# RoBeast_UI.net
KiCad netlist of a schematic drawn in Altium Designer
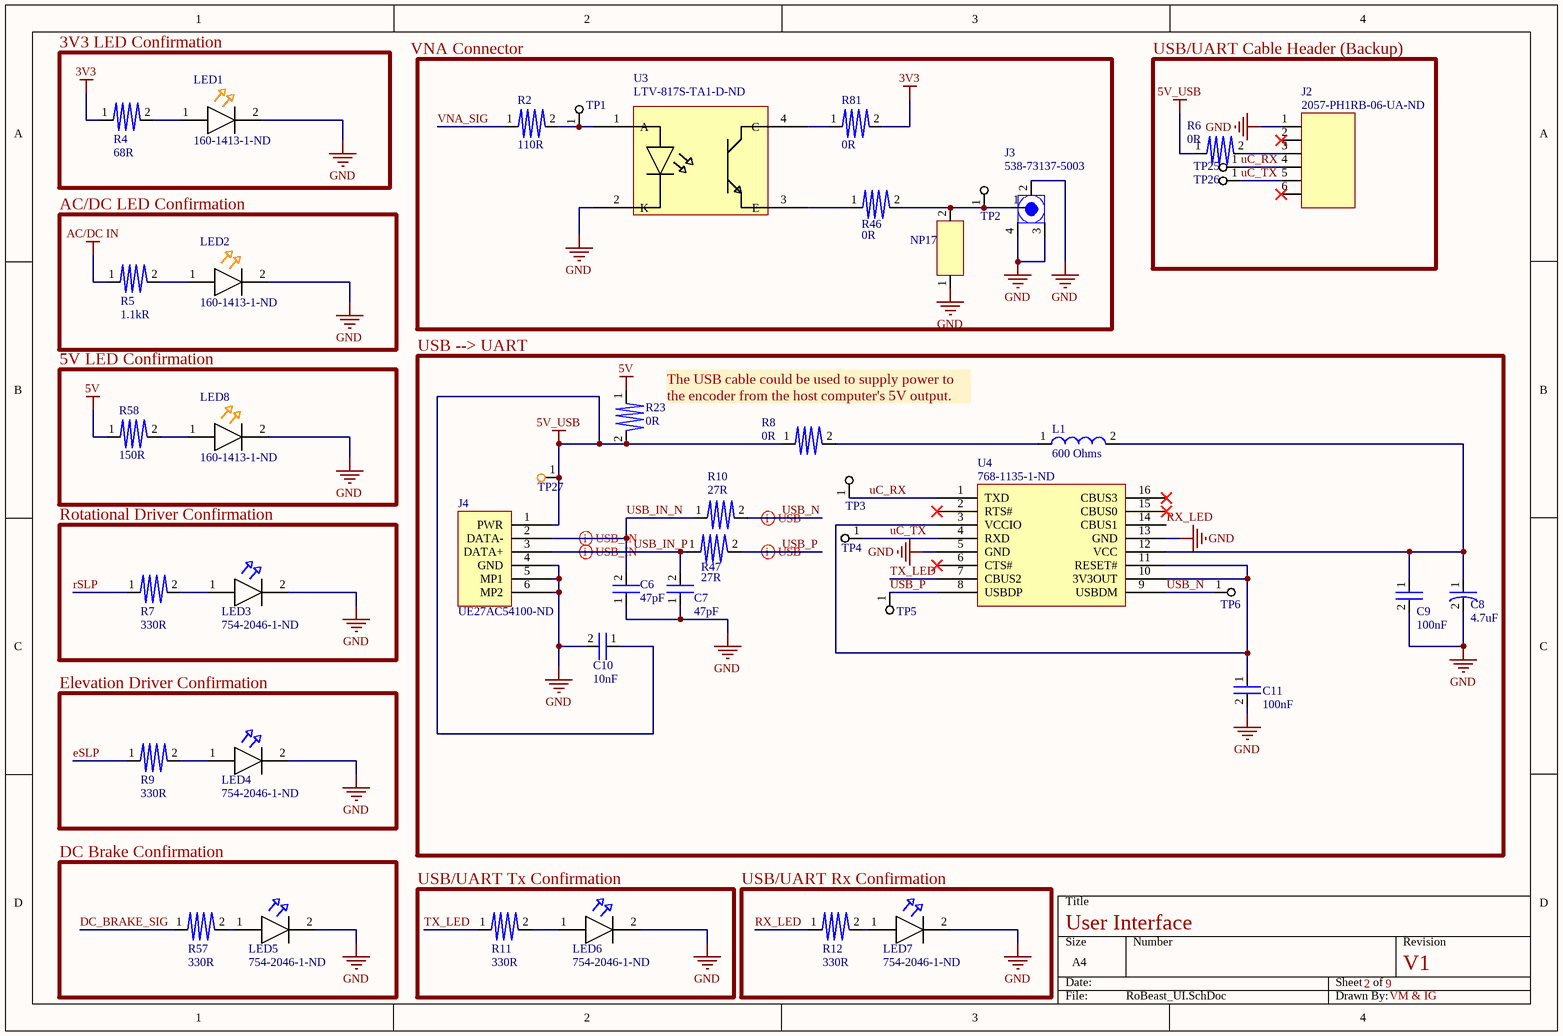
[diagram p0: RoBeast_UI.SchDoc]

(export (version "E")
  (design (tool "Eeschema 10.0.6"))
  (components
    (comp (ref "C6")
      (value "47pF")
      (footprint "0805")
      (fields
        (field (name "MANUFACTURER") "KEMET")
        (field (name "MANUFACTURER PART NUMBER") "C0805C470J5GAC7210")
      )
      (libsource (lib "RoBeast_Schematic_Library") (part "C0805C470J5GAC7210"))
    )
    (comp (ref "C7")
      (value "47pF")
      (footprint "0805")
      (fields
        (field (name "MANUFACTURER") "KEMET")
        (field (name "MANUFACTURER PART NUMBER") "C0805C470J5GAC7210")
      )
      (libsource (lib "RoBeast_Schematic_Library") (part "C0805C470J5GAC7210"))
    )
    (comp (ref "C8")
      (value "4.7uF")
      (footprint "EDK475M050A9DAA")
      (fields
        (field (name "MANUFACTURER") "KEMET")
        (field (name "MANUFACTURER PART NUMBER") "EDK475M050A9DAA")
      )
      (libsource (lib "RoBeast_Schematic_Library") (part "EDK475M050A9DAA"))
    )
    (comp (ref "C9")
      (value "100nF")
      (footprint "0805")
      (fields
        (field (name "MANUFACTURER") "KEMET")
        (field (name "MANUFACTURER PART NUMBER") "C0805C104J5RACTU")
      )
      (libsource (lib "RoBeast_Schematic_Library") (part "C0805C104J5RAC7800"))
    )
    (comp (ref "C10")
      (value "10nF")
      (footprint "0805")
      (fields
        (field (name "MANUFACTURER") "KEMET")
        (field (name "MANUFACTURER PART NUMBER") "C0805C103J5RAC7210")
      )
      (libsource (lib "RoBeast_Schematic_Library") (part "C0805C103J5RAC7210"))
    )
    (comp (ref "C11")
      (value "100nF")
      (footprint "0805")
      (fields
        (field (name "MANUFACTURER") "KEMET")
        (field (name "MANUFACTURER PART NUMBER") "C0805C104J5RACTU")
      )
      (libsource (lib "RoBeast_Schematic_Library") (part "C0805C104J5RAC7800"))
    )
    (comp (ref "J2")
      (value "6 Pin Connector")
      (footprint "PH1RB-06-UA")
      (description "Conn Unshrouded Header HDR 6 POS 2.54mm Solder RA Thru-Hole")
      (fields
        (field (name "MANUFACTURER") "Adam Equipment")
        (field (name "MANUFACTURER PART NUMBER") "PH1RB-06-UA")
        (field (name "SUPPLIER PART NUMBER 1") "2057-PH1RB-06-UA-ND")
      )
      (libsource (lib "RoBeast_Schematic_Library") (part "PH1RB-06-UA"))
    )
    (comp (ref "J3")
      (value "BNC Connector")
      (footprint "0731375003")
      (fields
        (field (name "MANUFACTURER") "Molex")
        (field (name "MANUFACTURER PART NUMBER") "73137-5003")
        (field (name "SUPPLIER PART NUMBER 1") "538-73137-5003")
      )
      (libsource (lib "RoBeast_Schematic_Library") (part "0731375003"))
    )
    (comp (ref "J4")
      (value "USB Connector")
      (footprint "UE27AC54100")
      (description "Conn USB 2.0 Type A RCP 4 POS 2mm/2.5mm Solder RA Thru-Hole 4 Terminal 1 Port")
      (fields
        (field (name "MANUFACTURER") "Amphenol ICC / FCI")
        (field (name "MANUFACTURER PART NUMBER") "UE27AC54100")
        (field (name "SUPPLIER PART NUMBER 1") "UE27AC54100-ND")
      )
      (libsource (lib "RoBeast_Schematic_Library") (part "UE27AC54100"))
    )
    (comp (ref "L1")
      (value "600 Ohms")
      (footprint "0805")
      (description "Ferrite Chip, 1 Function(s), 1.5A, 2 Pin(s)")
      (fields
        (field (name "MANUFACTURER PART NUMBER") "MI0805K601R-10")
        (field (name "MANUFACTURER") "Laird")
      )
      (libsource (lib "RoBeast_Schematic_Library") (part "MI0805K601R-10"))
    )
    (comp (ref "LED1")
      (value "Orange LED")
      (footprint "0805_LED")
      (description "Single Color LED, Orange, Water Clear, 1.4mm")
      (fields
        (field (name "MANUFACTURER") "Vishay Lite-On")
        (field (name "MANUFACTURER PART NUMBER") "LTST-C170KFKT")
        (field (name "SUPPLIER PART NUMBER 1") "160-1413-1-ND")
      )
      (libsource (lib "RoBeast_Schematic_Library") (part "LTST-C170KFKT"))
    )
    (comp (ref "LED2")
      (value "Orange LED")
      (footprint "0805_LED")
      (description "Single Color LED, Orange, Water Clear, 1.4mm")
      (fields
        (field (name "MANUFACTURER") "Vishay Lite-On")
        (field (name "MANUFACTURER PART NUMBER") "LTST-C170KFKT")
        (field (name "SUPPLIER PART NUMBER 1") "160-1413-1-ND")
      )
      (libsource (lib "RoBeast_Schematic_Library") (part "LTST-C170KFKT"))
    )
    (comp (ref "LED3")
      (value "Blue LED")
      (footprint "0805_LED")
      (description "Single Color LED")
      (fields
        (field (name "MANUFACTURER") "Kingbright")
        (field (name "MANUFACTURER PART NUMBER") "APTD2012LQBC/D")
        (field (name "SUPPLIER PART NUMBER 1") "754-2046-1-ND")
      )
      (libsource (lib "RoBeast_Schematic_Library") (part "APTD2012LQBC/D"))
    )
    (comp (ref "LED4")
      (value "Blue LED")
      (footprint "0805_LED")
      (description "Single Color LED")
      (fields
        (field (name "MANUFACTURER") "Kingbright")
        (field (name "MANUFACTURER PART NUMBER") "APTD2012LQBC/D")
        (field (name "SUPPLIER PART NUMBER 1") "754-2046-1-ND")
      )
      (libsource (lib "RoBeast_Schematic_Library") (part "APTD2012LQBC/D"))
    )
    (comp (ref "LED5")
      (value "Blue LED")
      (footprint "0805_LED")
      (description "Single Color LED")
      (fields
        (field (name "MANUFACTURER") "Kingbright")
        (field (name "MANUFACTURER PART NUMBER") "APTD2012LQBC/D")
        (field (name "SUPPLIER PART NUMBER 1") "754-2046-1-ND")
      )
      (libsource (lib "RoBeast_Schematic_Library") (part "APTD2012LQBC/D"))
    )
    (comp (ref "LED6")
      (value "Blue LED")
      (footprint "0805_LED")
      (description "Single Color LED")
      (fields
        (field (name "MANUFACTURER") "Kingbright")
        (field (name "MANUFACTURER PART NUMBER") "APTD2012LQBC/D")
        (field (name "SUPPLIER PART NUMBER 1") "754-2046-1-ND")
      )
      (libsource (lib "RoBeast_Schematic_Library") (part "APTD2012LQBC/D"))
    )
    (comp (ref "LED7")
      (value "Blue LED")
      (footprint "0805_LED")
      (description "Single Color LED")
      (fields
        (field (name "MANUFACTURER") "Kingbright")
        (field (name "MANUFACTURER PART NUMBER") "APTD2012LQBC/D")
        (field (name "SUPPLIER PART NUMBER 1") "754-2046-1-ND")
      )
      (libsource (lib "RoBeast_Schematic_Library") (part "APTD2012LQBC/D"))
    )
    (comp (ref "LED8")
      (value "Orange LED")
      (footprint "0805_LED")
      (description "Single Color LED, Orange, Water Clear, 1.4mm")
      (fields
        (field (name "MANUFACTURER") "Vishay Lite-On")
        (field (name "MANUFACTURER PART NUMBER") "LTST-C170KFKT")
        (field (name "SUPPLIER PART NUMBER 1") "160-1413-1-ND")
      )
      (libsource (lib "RoBeast_Schematic_Library") (part "LTST-C170KFKT"))
    )
    (comp (ref "NP17")
      (value "Not Populated")
      (footprint "0805")
      (libsource (lib "RoBeast_Schematic_Library") (part "NP"))
    )
    (comp (ref "R2")
      (value "110R")
      (footprint "0805")
      (fields
        (field (name "MANUFACTURER") "Yageo")
        (field (name "MANUFACTURER PART NUMBER") "AC0805FR-07110RL")
        (field (name "TOLERANCE") "1%")
      )
      (libsource (lib "RoBeast_Schematic_Library") (part "AC0805FR-07110RL"))
    )
    (comp (ref "R4")
      (value "68R")
      (footprint "0805")
      (fields
        (field (name "MANUFACTURER") "Yageo")
        (field (name "MANUFACTURER PART NUMBER") "RC0805FR-0768RL")
        (field (name "TOLERANCE") "1%")
      )
      (libsource (lib "RoBeast_Schematic_Library") (part "RC0805FR-0768RL"))
    )
    (comp (ref "R5")
      (value "1.1kR")
      (footprint "0805")
      (fields
        (field (name "MANUFACTURER") "Vishay Dale")
        (field (name "MANUFACTURER PART NUMBER") "RCS08051K10FKEA")
      )
      (libsource (lib "RoBeast_Schematic_Library") (part "RCS08051K10FKEA"))
    )
    (comp (ref "R6")
      (value "0R")
      (footprint "0805")
      (description "Fixed Resistor, Metal Glaze/thick Film, 0.125W, 0ohm, Surface Mount, 0805")
      (fields
        (field (name "MANUFACTURER") "Stackpole Electronics")
        (field (name "MANUFACTURER PART NUMBER") "RMCF0805ZT0R00")
      )
      (libsource (lib "RoBeast_Schematic_Library") (part "RMCF0805ZT0R00"))
    )
    (comp (ref "R7")
      (value "330R")
      (footprint "0805")
      (fields
        (field (name "MANUFACTURER") "Yageo")
        (field (name "MANUFACTURER PART NUMBER") "RC0805FR-13330RL")
        (field (name "TOLERANCE") "1%")
      )
      (libsource (lib "RoBeast_Schematic_Library") (part "RC0805FR-13330RL"))
    )
    (comp (ref "R8")
      (value "0R")
      (footprint "0805")
      (description "Fixed Resistor, Metal Glaze/thick Film, 0.125W, 0ohm, Surface Mount, 0805")
      (fields
        (field (name "MANUFACTURER") "Stackpole Electronics")
        (field (name "MANUFACTURER PART NUMBER") "RMCF0805ZT0R00")
      )
      (libsource (lib "RoBeast_Schematic_Library") (part "RMCF0805ZT0R00"))
    )
    (comp (ref "R9")
      (value "330R")
      (footprint "0805")
      (fields
        (field (name "MANUFACTURER") "Yageo")
        (field (name "MANUFACTURER PART NUMBER") "RC0805FR-13330RL")
        (field (name "TOLERANCE") "1%")
      )
      (libsource (lib "RoBeast_Schematic_Library") (part "RC0805FR-13330RL"))
    )
    (comp (ref "R10")
      (value "27R")
      (footprint "0805")
      (fields
        (field (name "MANUFACTURER") "KOA Speer")
        (field (name "MANUFACTURER PART NUMBER") "SG73P2ATTD27R0F")
        (field (name "TOLERANCE") "1%")
      )
      (libsource (lib "RoBeast_Schematic_Library") (part "SG73P2ATTD27R0F"))
    )
    (comp (ref "R11")
      (value "330R")
      (footprint "0805")
      (fields
        (field (name "MANUFACTURER") "Yageo")
        (field (name "MANUFACTURER PART NUMBER") "RC0805FR-13330RL")
        (field (name "TOLERANCE") "1%")
      )
      (libsource (lib "RoBeast_Schematic_Library") (part "RC0805FR-13330RL"))
    )
    (comp (ref "R12")
      (value "330R")
      (footprint "0805")
      (fields
        (field (name "MANUFACTURER") "Yageo")
        (field (name "MANUFACTURER PART NUMBER") "RC0805FR-13330RL")
        (field (name "TOLERANCE") "1%")
      )
      (libsource (lib "RoBeast_Schematic_Library") (part "RC0805FR-13330RL"))
    )
    (comp (ref "R23")
      (value "0R")
      (footprint "0805")
      (description "Fixed Resistor, Metal Glaze/thick Film, 0.125W, 0ohm, Surface Mount, 0805")
      (fields
        (field (name "MANUFACTURER") "Stackpole Electronics")
        (field (name "MANUFACTURER PART NUMBER") "RMCF0805ZT0R00")
      )
      (libsource (lib "RoBeast_Schematic_Library") (part "RMCF0805ZT0R00"))
    )
    (comp (ref "R46")
      (value "0R")
      (footprint "0805")
      (description "Fixed Resistor, Metal Glaze/thick Film, 0.125W, 0ohm, Surface Mount, 0805")
      (fields
        (field (name "MANUFACTURER") "Stackpole Electronics")
        (field (name "MANUFACTURER PART NUMBER") "RMCF0805ZT0R00")
      )
      (libsource (lib "RoBeast_Schematic_Library") (part "RMCF0805ZT0R00"))
    )
    (comp (ref "R47")
      (value "27R")
      (footprint "0805")
      (fields
        (field (name "MANUFACTURER") "KOA Speer")
        (field (name "MANUFACTURER PART NUMBER") "SG73P2ATTD27R0F")
        (field (name "TOLERANCE") "1%")
      )
      (libsource (lib "RoBeast_Schematic_Library") (part "SG73P2ATTD27R0F"))
    )
    (comp (ref "R57")
      (value "330R")
      (footprint "0805")
      (fields
        (field (name "MANUFACTURER") "Yageo")
        (field (name "MANUFACTURER PART NUMBER") "RC0805FR-13330RL")
        (field (name "TOLERANCE") "1%")
      )
      (libsource (lib "RoBeast_Schematic_Library") (part "RC0805FR-13330RL"))
    )
    (comp (ref "R58")
      (value "150R")
      (footprint "0805")
      (fields
        (field (name "MANUFACTURER") "TE Connectivity")
        (field (name "MANUFACTURER PART NUMBER") "CRGP0805F150R")
      )
      (libsource (lib "RoBeast_Schematic_Library") (part "CRGP0805F150R"))
    )
    (comp (ref "R81")
      (value "0R")
      (footprint "0805")
      (description "Fixed Resistor, Metal Glaze/thick Film, 0.125W, 0ohm, Surface Mount, 0805")
      (fields
        (field (name "MANUFACTURER") "Stackpole Electronics")
        (field (name "MANUFACTURER PART NUMBER") "RMCF0805ZT0R00")
      )
      (libsource (lib "RoBeast_Schematic_Library") (part "RMCF0805ZT0R00"))
    )
    (comp (ref "TP1")
      (value "Test Point")
      (footprint "RCWCTE")
      (description "Testing/Accessories")
      (fields (field (name "MANUFACTURER") "KOA Speer") (field (name "MANUFACTURER PART NUMBER") "RCWCTE"))
      (libsource (lib "RoBeast_Schematic_Library") (part "RCWCTE"))
    )
    (comp (ref "TP2")
      (value "Test Point")
      (footprint "RCWCTE")
      (description "Testing/Accessories")
      (fields (field (name "MANUFACTURER") "KOA Speer") (field (name "MANUFACTURER PART NUMBER") "RCWCTE"))
      (libsource (lib "RoBeast_Schematic_Library") (part "RCWCTE"))
    )
    (comp (ref "TP3")
      (value "Test Point")
      (footprint "RCWCTE")
      (description "Testing/Accessories")
      (fields (field (name "MANUFACTURER") "KOA Speer") (field (name "MANUFACTURER PART NUMBER") "RCWCTE"))
      (libsource (lib "RoBeast_Schematic_Library") (part "RCWCTE"))
    )
    (comp (ref "TP4")
      (value "Test Point")
      (footprint "RCWCTE")
      (description "Testing/Accessories")
      (fields (field (name "MANUFACTURER") "KOA Speer") (field (name "MANUFACTURER PART NUMBER") "RCWCTE"))
      (libsource (lib "RoBeast_Schematic_Library") (part "RCWCTE"))
    )
    (comp (ref "TP5")
      (value "Test Point")
      (footprint "RCWCTE")
      (description "Testing/Accessories")
      (fields (field (name "MANUFACTURER") "KOA Speer") (field (name "MANUFACTURER PART NUMBER") "RCWCTE"))
      (libsource (lib "RoBeast_Schematic_Library") (part "RCWCTE"))
    )
    (comp (ref "TP6")
      (value "Test Point")
      (footprint "RCWCTE")
      (description "Testing/Accessories")
      (fields (field (name "MANUFACTURER") "KOA Speer") (field (name "MANUFACTURER PART NUMBER") "RCWCTE"))
      (libsource (lib "RoBeast_Schematic_Library") (part "RCWCTE"))
    )
    (comp (ref "TP25")
      (value "Test Point")
      (footprint "RCWCTE")
      (description "Testing/Accessories")
      (fields (field (name "MANUFACTURER") "KOA Speer") (field (name "MANUFACTURER PART NUMBER") "RCWCTE"))
      (libsource (lib "RoBeast_Schematic_Library") (part "RCWCTE"))
    )
    (comp (ref "TP26")
      (value "Test Point")
      (footprint "RCWCTE")
      (description "Testing/Accessories")
      (fields (field (name "MANUFACTURER") "KOA Speer") (field (name "MANUFACTURER PART NUMBER") "RCWCTE"))
      (libsource (lib "RoBeast_Schematic_Library") (part "RCWCTE"))
    )
    (comp (ref "TP27")
      (value "Test Point")
      (footprint "Test Point")
      (libsource (lib "RoBeast_Schematic_Library") (part "Test Point"))
    )
    (comp (ref "U3")
      (value "Optoisolator")
      (footprint "LTV-817S-TA")
      (description "Transistor Output Optocoupler, 1-Element, 5000V Isolation")
      (fields
        (field (name "MANUFACTURER") "Vishay Lite-On")
        (field (name "MANUFACTURER PART NUMBER") "LTV-817S-TA1-D")
        (field (name "SUPPLIER PART NUMBER 1") "LTV-817S-TA1-D-ND")
      )
      (libsource (lib "RoBeast_Schematic_Library") (part "LTV-817S-TA"))
    )
    (comp (ref "U4")
      (value "USB/UART Converter")
      (footprint "FT230XS-R")
      (description "Microprocessor Circuit, CMOS, PDSO16")
      (fields
        (field (name "MANUFACTURER") "FTDI")
        (field (name "MANUFACTURER PART NUMBER") "FT230XS-R")
        (field (name "SUPPLIER PART NUMBER 1") "768-1135-1-ND")
      )
      (libsource (lib "RoBeast_Schematic_Library") (part "FT230XS-R"))
    )
  )
  (nets
    (net (code "1") (name "/DC_BRAKE_SIG") (class "Default")
      (node (ref "R57") (pin "1") (pinfunction "1_1") (pintype "passive"))
    )
    (net (code "2") (name "/RX_LED") (class "Default")
      (node (ref "R12") (pin "1") (pinfunction "1_1") (pintype "passive"))
      (node (ref "U4") (pin "14") (pinfunction "CBUS1_14") (pintype "passive"))
    )
    (net (code "3") (name "/TX_LED") (class "Default")
      (node (ref "R11") (pin "1") (pinfunction "1_1") (pintype "passive"))
      (node (ref "U4") (pin "7") (pinfunction "CBUS2_7") (pintype "passive"))
    )
    (net (code "4") (name "/USB_IN_N") (class "Default")
      (node (ref "C6") (pin "2") (pinfunction "2_2") (pintype "passive"))
      (node (ref "J4") (pin "2") (pinfunction "DATA-_2") (pintype "passive"))
      (node (ref "R10") (pin "1") (pinfunction "1_1") (pintype "passive"))
    )
    (net (code "5") (name "/USB_IN_P") (class "Default")
      (node (ref "C7") (pin "2") (pinfunction "2_2") (pintype "passive"))
      (node (ref "J4") (pin "3") (pinfunction "DATA+_3") (pintype "passive"))
      (node (ref "R47") (pin "1") (pinfunction "1_1") (pintype "passive"))
    )
    (net (code "6") (name "/USB_N") (class "Default")
      (node (ref "R10") (pin "2") (pinfunction "2_2") (pintype "passive"))
      (node (ref "TP6") (pin "1") (pinfunction "1_1") (pintype "passive"))
      (node (ref "U4") (pin "9") (pinfunction "USBDM_9") (pintype "passive"))
    )
    (net (code "7") (name "/USB_P") (class "Default")
      (node (ref "R47") (pin "2") (pinfunction "2_2") (pintype "passive"))
      (node (ref "TP5") (pin "1") (pinfunction "1_1") (pintype "passive"))
      (node (ref "U4") (pin "8") (pinfunction "USBDP_8") (pintype "passive"))
    )
    (net (code "8") (name "/VNA_SIG") (class "Default")
      (node (ref "R2") (pin "1") (pinfunction "1_1") (pintype "passive"))
    )
    (net (code "9") (name "/eSLP") (class "Default")
      (node (ref "R9") (pin "1") (pinfunction "1_1") (pintype "passive"))
    )
    (net (code "10") (name "/rSLP") (class "Default")
      (node (ref "R7") (pin "1") (pinfunction "1_1") (pintype "passive"))
    )
    (net (code "11") (name "/uC_RX") (class "Default")
      (node (ref "J2") (pin "4") (pinfunction "4_4") (pintype "passive"))
      (node (ref "TP25") (pin "1") (pinfunction "1_1") (pintype "passive"))
      (node (ref "TP3") (pin "1") (pinfunction "1_1") (pintype "passive"))
      (node (ref "U4") (pin "1") (pinfunction "TXD_1") (pintype "passive"))
    )
    (net (code "12") (name "/uC_TX") (class "Default")
      (node (ref "J2") (pin "5") (pinfunction "5_5") (pintype "passive"))
      (node (ref "TP26") (pin "1") (pinfunction "1_1") (pintype "passive"))
      (node (ref "TP4") (pin "1") (pinfunction "1_1") (pintype "passive"))
      (node (ref "U4") (pin "4") (pinfunction "RXD_4") (pintype "passive"))
    )
    (net (code "13") (name "3V3") (class "Default")
      (node (ref "R4") (pin "1") (pinfunction "1_1") (pintype "passive"))
      (node (ref "R81") (pin "2") (pinfunction "2_2") (pintype "passive"))
    )
    (net (code "14") (name "5V") (class "Default")
      (node (ref "R23") (pin "1") (pinfunction "1_1") (pintype "passive"))
      (node (ref "R58") (pin "1") (pinfunction "1_1") (pintype "passive"))
    )
    (net (code "15") (name "5V_USB") (class "Default")
      (node (ref "C10") (pin "1") (pinfunction "1_1") (pintype "passive"))
      (node (ref "J4") (pin "1") (pinfunction "PWR_1") (pintype "passive"))
      (node (ref "R23") (pin "2") (pinfunction "2_2") (pintype "passive"))
      (node (ref "R6") (pin "1") (pinfunction "1_1") (pintype "passive"))
      (node (ref "R8") (pin "1") (pinfunction "1_1") (pintype "passive"))
      (node (ref "TP27") (pin "1") (pinfunction "1_1") (pintype "passive"))
    )
    (net (code "16") (name "AC{slash}DC IN") (class "Default")
      (node (ref "R5") (pin "1") (pinfunction "1_1") (pintype "passive"))
    )
    (net (code "17") (name "GND") (class "Default")
      (node (ref "C10") (pin "2") (pinfunction "2_2") (pintype "passive"))
      (node (ref "C11") (pin "2") (pinfunction "2_2") (pintype "passive"))
      (node (ref "C6") (pin "1") (pinfunction "1_1") (pintype "passive"))
      (node (ref "C7") (pin "1") (pinfunction "1_1") (pintype "passive"))
      (node (ref "C8") (pin "2") (pinfunction "2_2") (pintype "passive"))
      (node (ref "C9") (pin "2") (pinfunction "2_2") (pintype "passive"))
      (node (ref "J2") (pin "1") (pinfunction "1_1") (pintype "passive"))
      (node (ref "J3") (pin "2") (pinfunction "GND_2") (pintype "passive"))
      (node (ref "J3") (pin "3") (pinfunction "SUP_3") (pintype "passive"))
      (node (ref "J3") (pin "4") (pinfunction "SUP_4") (pintype "passive"))
      (node (ref "J4") (pin "4") (pinfunction "GND_4") (pintype "passive"))
      (node (ref "J4") (pin "5") (pinfunction "MP1_5") (pintype "passive"))
      (node (ref "J4") (pin "6") (pinfunction "MP2_6") (pintype "passive"))
      (node (ref "LED1") (pin "2") (pinfunction "K_2") (pintype "passive"))
      (node (ref "LED2") (pin "2") (pinfunction "K_2") (pintype "passive"))
      (node (ref "LED3") (pin "2") (pinfunction "K_2") (pintype "passive"))
      (node (ref "LED4") (pin "2") (pinfunction "K_2") (pintype "passive"))
      (node (ref "LED5") (pin "2") (pinfunction "K_2") (pintype "passive"))
      (node (ref "LED6") (pin "2") (pinfunction "K_2") (pintype "passive"))
      (node (ref "LED7") (pin "2") (pinfunction "K_2") (pintype "passive"))
      (node (ref "LED8") (pin "2") (pinfunction "K_2") (pintype "passive"))
      (node (ref "NP17") (pin "1") (pinfunction "1_1") (pintype "passive"))
      (node (ref "U3") (pin "2") (pinfunction "K_2") (pintype "passive"))
      (node (ref "U4") (pin "13") (pinfunction "GND_13") (pintype "passive"))
      (node (ref "U4") (pin "5") (pinfunction "GND_5") (pintype "passive"))
    )
    (net (code "18") (name "Net-(J2-Pad3)") (class "Default")
      (node (ref "J2") (pin "3") (pinfunction "3_3") (pintype "passive"))
      (node (ref "R6") (pin "2") (pinfunction "2_2") (pintype "passive"))
    )
    (net (code "19") (name "Net-(J3-SIGN)") (class "Default")
      (node (ref "J3") (pin "1") (pinfunction "SIGN_1") (pintype "passive"))
      (node (ref "NP17") (pin "2") (pinfunction "2_2") (pintype "passive"))
      (node (ref "R46") (pin "2") (pinfunction "2_2") (pintype "passive"))
      (node (ref "TP2") (pin "1") (pinfunction "1_1") (pintype "passive"))
    )
    (net (code "20") (name "Net-(L1-Pad1)") (class "Default")
      (node (ref "L1") (pin "1") (pinfunction "1_1") (pintype "passive"))
      (node (ref "R8") (pin "2") (pinfunction "2_2") (pintype "passive"))
    )
    (net (code "21") (name "Net-(LED1-A)") (class "Default")
      (node (ref "LED1") (pin "1") (pinfunction "A_1") (pintype "passive"))
      (node (ref "R4") (pin "2") (pinfunction "2_2") (pintype "passive"))
    )
    (net (code "22") (name "Net-(LED2-A)") (class "Default")
      (node (ref "LED2") (pin "1") (pinfunction "A_1") (pintype "passive"))
      (node (ref "R5") (pin "2") (pinfunction "2_2") (pintype "passive"))
    )
    (net (code "23") (name "Net-(LED3-A)") (class "Default")
      (node (ref "LED3") (pin "1") (pinfunction "A_1") (pintype "passive"))
      (node (ref "R7") (pin "2") (pinfunction "2_2") (pintype "passive"))
    )
    (net (code "24") (name "Net-(LED4-A)") (class "Default")
      (node (ref "LED4") (pin "1") (pinfunction "A_1") (pintype "passive"))
      (node (ref "R9") (pin "2") (pinfunction "2_2") (pintype "passive"))
    )
    (net (code "25") (name "Net-(LED5-A)") (class "Default")
      (node (ref "LED5") (pin "1") (pinfunction "A_1") (pintype "passive"))
      (node (ref "R57") (pin "2") (pinfunction "2_2") (pintype "passive"))
    )
    (net (code "26") (name "Net-(LED6-A)") (class "Default")
      (node (ref "LED6") (pin "1") (pinfunction "A_1") (pintype "passive"))
      (node (ref "R11") (pin "2") (pinfunction "2_2") (pintype "passive"))
    )
    (net (code "27") (name "Net-(LED7-A)") (class "Default")
      (node (ref "LED7") (pin "1") (pinfunction "A_1") (pintype "passive"))
      (node (ref "R12") (pin "2") (pinfunction "2_2") (pintype "passive"))
    )
    (net (code "28") (name "Net-(LED8-A)") (class "Default")
      (node (ref "LED8") (pin "1") (pinfunction "A_1") (pintype "passive"))
      (node (ref "R58") (pin "2") (pinfunction "2_2") (pintype "passive"))
    )
    (net (code "29") (name "Net-(U3-A)") (class "Default")
      (node (ref "R2") (pin "2") (pinfunction "2_2") (pintype "passive"))
      (node (ref "TP1") (pin "1") (pinfunction "1_1") (pintype "passive"))
      (node (ref "U3") (pin "1") (pinfunction "A_1") (pintype "passive"))
    )
    (net (code "30") (name "Net-(U3-C)") (class "Default")
      (node (ref "R81") (pin "1") (pinfunction "1_1") (pintype "passive"))
      (node (ref "U3") (pin "4") (pinfunction "C_4") (pintype "passive"))
    )
    (net (code "31") (name "Net-(U3-E)") (class "Default")
      (node (ref "R46") (pin "1") (pinfunction "1_1") (pintype "passive"))
      (node (ref "U3") (pin "3") (pinfunction "E_3") (pintype "passive"))
    )
    (net (code "32") (name "Net-(U4-3V3OUT)") (class "Default")
      (node (ref "C11") (pin "1") (pinfunction "1_1") (pintype "passive"))
      (node (ref "U4") (pin "10") (pinfunction "3V3OUT_10") (pintype "passive"))
      (node (ref "U4") (pin "11") (pinfunction "RESET#_11") (pintype "passive"))
      (node (ref "U4") (pin "3") (pinfunction "VCCIO_3") (pintype "passive"))
    )
    (net (code "33") (name "Net-(U4-VCC)") (class "Default")
      (node (ref "C8") (pin "1") (pinfunction "1_1") (pintype "passive"))
      (node (ref "C9") (pin "1") (pinfunction "1_1") (pintype "passive"))
      (node (ref "L1") (pin "2") (pinfunction "2_2") (pintype "passive"))
      (node (ref "U4") (pin "12") (pinfunction "VCC_12") (pintype "passive"))
    )
    (net (code "34") (name "unconnected-(J2-Pad2)") (class "Default")
      (node (ref "J2") (pin "2") (pinfunction "2_2") (pintype "passive+no_connect"))
    )
    (net (code "35") (name "unconnected-(J2-Pad6)") (class "Default")
      (node (ref "J2") (pin "6") (pinfunction "6_6") (pintype "passive+no_connect"))
    )
    (net (code "36") (name "unconnected-(U4-CBUS0-Pad15)") (class "Default")
      (node (ref "U4") (pin "15") (pinfunction "CBUS0_15") (pintype "passive+no_connect"))
    )
    (net (code "37") (name "unconnected-(U4-CBUS3-Pad16)") (class "Default")
      (node (ref "U4") (pin "16") (pinfunction "CBUS3_16") (pintype "passive+no_connect"))
    )
    (net (code "38") (name "unconnected-(U4-CTS#-Pad6)") (class "Default")
      (node (ref "U4") (pin "6") (pinfunction "CTS#_6") (pintype "passive+no_connect"))
    )
    (net (code "39") (name "unconnected-(U4-RTS#-Pad2)") (class "Default")
      (node (ref "U4") (pin "2") (pinfunction "RTS#_2") (pintype "passive+no_connect"))
    )
  )
)
